# Encoder_board.net
KiCad netlist of a schematic drawn in EAGLE
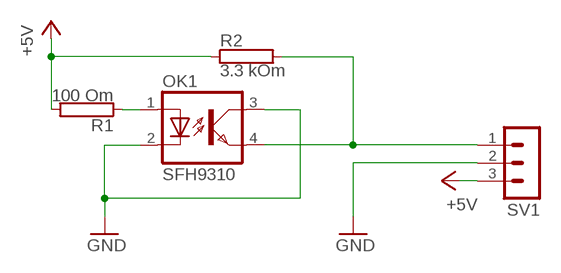
[diagram p0: schematic, sheet 1]

(export (version "E")
  (design (tool "Eeschema 10.0.6"))
  (components
    (comp (ref "OK1")
      (value "SFH9310")
      (footprint "eagle-import:SFH9310")
      (libsource (lib "eagle-import") (part "SFH9310"))
    )
    (comp (ref "R1")
      (value "100 Om")
      (footprint "eagle-import:RS1_4")
      (fields (field (name "MF") "OHMITE") (field (name "MPN") "RRS1K0"))
      (libsource (lib "eagle-import") (part "RRS1/4"))
    )
    (comp (ref "R2")
      (value "3.3 kOm")
      (footprint "eagle-import:RS1_4")
      (fields (field (name "MF") "OHMITE") (field (name "MPN") "RRS1K0"))
      (libsource (lib "eagle-import") (part "RRS1/4"))
    )
    (comp (ref "SV1")
      (value "MA03-1")
      (footprint "eagle-import:MA03-1")
      (libsource (lib "eagle-import") (part "MA03-1"))
    )
  )
  (nets
    (net (code "1") (name "+5V") (class "Default")
      (node (ref "R1") (pin "2") (pinfunction "2_2") (pintype "passive"))
      (node (ref "R2") (pin "1") (pinfunction "1_1") (pintype "passive"))
      (node (ref "SV1") (pin "3") (pinfunction "3_3") (pintype "passive"))
    )
    (net (code "2") (name "GND") (class "Default")
      (node (ref "OK1") (pin "2") (pinfunction "C_2") (pintype "passive"))
      (node (ref "OK1") (pin "3") (pinfunction "COL_3") (pintype "passive"))
      (node (ref "SV1") (pin "2") (pinfunction "2_2") (pintype "passive"))
    )
    (net (code "3") (name "Net-(OK1-A)") (class "Default")
      (node (ref "OK1") (pin "1") (pinfunction "A_1") (pintype "passive"))
      (node (ref "R1") (pin "1") (pinfunction "1_1") (pintype "passive"))
    )
    (net (code "4") (name "Net-(OK1-EMIT)") (class "Default")
      (node (ref "OK1") (pin "4") (pinfunction "EMIT_4") (pintype "passive"))
      (node (ref "R2") (pin "2") (pinfunction "2_2") (pintype "passive"))
      (node (ref "SV1") (pin "1") (pinfunction "1_1") (pintype "passive"))
    )
  )
)
